# umodular_mega_shield_rev02.net
KiCad netlist of a schematic drawn in EAGLE
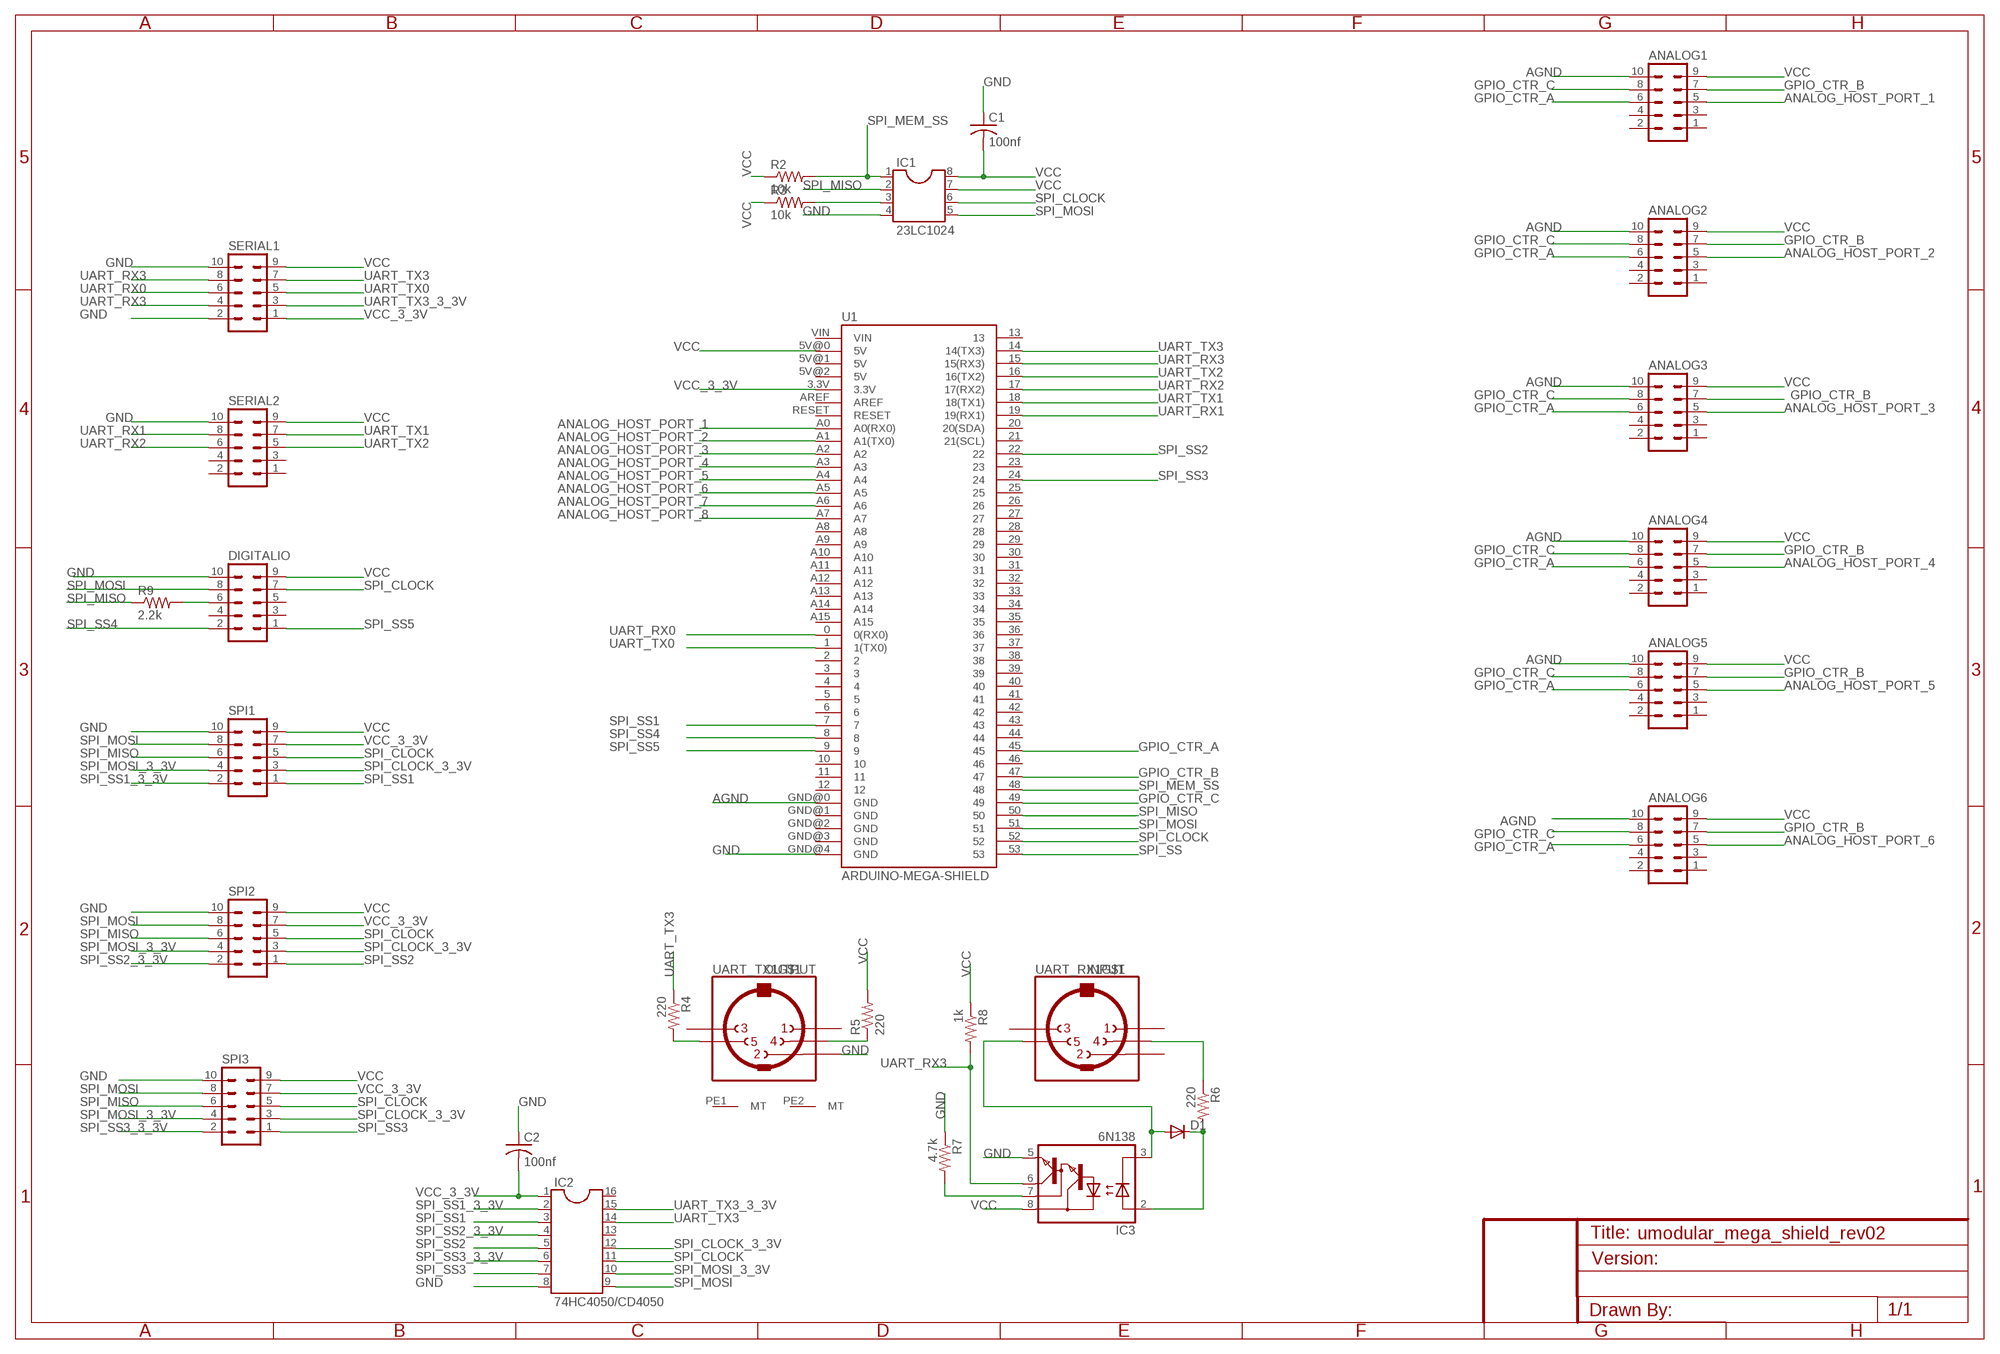
[diagram p0: schematic, sheet 1]

(export (version "E")
  (design (tool "Eeschema 10.0.6"))
  (components
    (comp (ref "ANALOG1")
      (value "MA05-2")
      (footprint "eagle-import:MA05-2")
      (libsource (lib "eagle-import") (part "MA05-2"))
    )
    (comp (ref "ANALOG2")
      (value "MA05-2")
      (footprint "eagle-import:MA05-2")
      (libsource (lib "eagle-import") (part "MA05-2"))
    )
    (comp (ref "ANALOG3")
      (value "MA05-2")
      (footprint "eagle-import:MA05-2")
      (libsource (lib "eagle-import") (part "MA05-2"))
    )
    (comp (ref "ANALOG4")
      (value "MA05-2")
      (footprint "eagle-import:MA05-2")
      (libsource (lib "eagle-import") (part "MA05-2"))
    )
    (comp (ref "ANALOG5")
      (value "MA05-2")
      (footprint "eagle-import:MA05-2")
      (libsource (lib "eagle-import") (part "MA05-2"))
    )
    (comp (ref "ANALOG6")
      (value "MA05-2")
      (footprint "eagle-import:MA05-2")
      (libsource (lib "eagle-import") (part "MA05-2"))
    )
    (comp (ref "C1")
      (value "100nf")
      (footprint "eagle-import:C050-024X044")
      (libsource (lib "eagle-import") (part "C-US050-024X044"))
    )
    (comp (ref "C2")
      (value "100nf")
      (footprint "eagle-import:C050-024X044")
      (libsource (lib "eagle-import") (part "C-US050-024X044"))
    )
    (comp (ref "D1")
      (value "1N4148DO35-7")
      (footprint "eagle-import:DO35-7")
      (libsource (lib "eagle-import") (part "1N4148DO35-7"))
    )
    (comp (ref "DIGITALIO")
      (value "MA05-2")
      (footprint "eagle-import:MA05-2")
      (libsource (lib "eagle-import") (part "MA05-2"))
    )
    (comp (ref "IC1")
      (value "23LC1024")
      (footprint "eagle-import:DIL08")
      (libsource (lib "eagle-import") (part "DIL8"))
    )
    (comp (ref "IC2")
      (value "74HC4050/CD4050")
      (footprint "eagle-import:DIL16")
      (libsource (lib "eagle-import") (part "DIL16"))
    )
    (comp (ref "IC3")
      (value "6N138")
      (footprint "eagle-import:DIL08")
      (fields (field (name "MF") "VISHAY/TELEFUNKEN"))
      (libsource (lib "eagle-import") (part "6N138"))
    )
    (comp (ref "R2")
      (value "10k")
      (footprint "eagle-import:0204_7@1")
      (libsource (lib "eagle-import") (part "R-US_0204/7"))
    )
    (comp (ref "R3")
      (value "10k")
      (footprint "eagle-import:0204_7@1")
      (libsource (lib "eagle-import") (part "R-US_0204/7"))
    )
    (comp (ref "R4")
      (value "220")
      (footprint "eagle-import:0204_7@1")
      (libsource (lib "eagle-import") (part "R-US_0204/7"))
    )
    (comp (ref "R5")
      (value "220")
      (footprint "eagle-import:0204_7@1")
      (libsource (lib "eagle-import") (part "R-US_0204/7"))
    )
    (comp (ref "R6")
      (value "220")
      (footprint "eagle-import:0204_7@1")
      (libsource (lib "eagle-import") (part "R-US_0204/7"))
    )
    (comp (ref "R7")
      (value "4.7k")
      (footprint "eagle-import:0204_7@1")
      (libsource (lib "eagle-import") (part "R-US_0204/7"))
    )
    (comp (ref "R8")
      (value "1k")
      (footprint "eagle-import:0204_7@1")
      (libsource (lib "eagle-import") (part "R-US_0204/7"))
    )
    (comp (ref "R9")
      (value "2.2k")
      (footprint "eagle-import:0204_7@1")
      (libsource (lib "eagle-import") (part "R-US_0204/7"))
    )
    (comp (ref "SERIAL1")
      (value "MA05-2")
      (footprint "eagle-import:MA05-2")
      (libsource (lib "eagle-import") (part "MA05-2"))
    )
    (comp (ref "SERIAL2")
      (value "MA05-2")
      (footprint "eagle-import:MA05-2")
      (libsource (lib "eagle-import") (part "MA05-2"))
    )
    (comp (ref "SPI1")
      (value "MA05-2")
      (footprint "eagle-import:MA05-2")
      (libsource (lib "eagle-import") (part "MA05-2"))
    )
    (comp (ref "SPI2")
      (value "MA05-2")
      (footprint "eagle-import:MA05-2")
      (libsource (lib "eagle-import") (part "MA05-2"))
    )
    (comp (ref "SPI3")
      (value "MA05-2")
      (footprint "eagle-import:MA05-2")
      (libsource (lib "eagle-import") (part "MA05-2"))
    )
    (comp (ref "U1")
      (value "ARDUINO-MEGA-SHIELD")
      (footprint "eagle-import:ARDUINO_MEGA@1")
      (libsource (lib "eagle-import") (part "ARDUINO-MEGAFULL"))
    )
    (comp (ref "UART_RX1")
      (value "INPUT")
      (footprint "eagle-import:CP-2350")
      (libsource (lib "eagle-import") (part "MIDIJACK"))
    )
    (comp (ref "UART_TX1")
      (value "OUTPUT")
      (footprint "eagle-import:CP-2350")
      (libsource (lib "eagle-import") (part "MIDIJACK"))
    )
  )
  (nets
    (net (code "1") (name "/AGND") (class "Default")
      (node (ref "ANALOG1") (pin "10") (pinfunction "10_10") (pintype "passive"))
      (node (ref "ANALOG2") (pin "10") (pinfunction "10_10") (pintype "passive"))
      (node (ref "ANALOG3") (pin "10") (pinfunction "10_10") (pintype "passive"))
      (node (ref "ANALOG4") (pin "10") (pinfunction "10_10") (pintype "passive"))
      (node (ref "ANALOG5") (pin "10") (pinfunction "10_10") (pintype "passive"))
      (node (ref "ANALOG6") (pin "10") (pinfunction "10_10") (pintype "passive"))
      (node (ref "U1") (pin "GND@0") (pinfunction "GND_GND@0") (pintype "bidirectional"))
    )
    (net (code "2") (name "/ANALOG_HOST_PORT_1") (class "Default")
      (node (ref "ANALOG1") (pin "5") (pinfunction "5_5") (pintype "passive"))
      (node (ref "U1") (pin "A0") (pinfunction "A0(RX0)_A0") (pintype "bidirectional"))
    )
    (net (code "3") (name "/ANALOG_HOST_PORT_2") (class "Default")
      (node (ref "ANALOG2") (pin "5") (pinfunction "5_5") (pintype "passive"))
      (node (ref "U1") (pin "A1") (pinfunction "A1(TX0)_A1") (pintype "bidirectional"))
    )
    (net (code "4") (name "/ANALOG_HOST_PORT_3") (class "Default")
      (node (ref "ANALOG3") (pin "5") (pinfunction "5_5") (pintype "passive"))
      (node (ref "U1") (pin "A2") (pinfunction "A2_A2") (pintype "bidirectional"))
    )
    (net (code "5") (name "/ANALOG_HOST_PORT_4") (class "Default")
      (node (ref "ANALOG4") (pin "5") (pinfunction "5_5") (pintype "passive"))
      (node (ref "U1") (pin "A3") (pinfunction "A3_A3") (pintype "bidirectional"))
    )
    (net (code "6") (name "/ANALOG_HOST_PORT_5") (class "Default")
      (node (ref "ANALOG5") (pin "5") (pinfunction "5_5") (pintype "passive"))
      (node (ref "U1") (pin "A4") (pinfunction "A4_A4") (pintype "bidirectional"))
    )
    (net (code "7") (name "/ANALOG_HOST_PORT_6") (class "Default")
      (node (ref "ANALOG6") (pin "5") (pinfunction "5_5") (pintype "passive"))
      (node (ref "U1") (pin "A5") (pinfunction "A5_A5") (pintype "bidirectional"))
    )
    (net (code "8") (name "/ANALOG_HOST_PORT_7") (class "Default")
      (node (ref "U1") (pin "A6") (pinfunction "A6_A6") (pintype "bidirectional"))
    )
    (net (code "9") (name "/ANALOG_HOST_PORT_8") (class "Default")
      (node (ref "U1") (pin "A7") (pinfunction "A7_A7") (pintype "bidirectional"))
    )
    (net (code "10") (name "/GND") (class "Default")
      (node (ref "C1") (pin "1") (pinfunction "1_1") (pintype "passive"))
      (node (ref "C2") (pin "1") (pinfunction "1_1") (pintype "passive"))
      (node (ref "DIGITALIO") (pin "10") (pinfunction "10_10") (pintype "passive"))
      (node (ref "IC1") (pin "4") (pinfunction "4_4") (pintype "passive"))
      (node (ref "IC2") (pin "8") (pinfunction "8_8") (pintype "passive"))
      (node (ref "IC3") (pin "5") (pinfunction "GND_5") (pintype "passive"))
      (node (ref "R7") (pin "1") (pinfunction "1_1") (pintype "passive"))
      (node (ref "SERIAL1") (pin "10") (pinfunction "10_10") (pintype "passive"))
      (node (ref "SERIAL1") (pin "2") (pinfunction "2_2") (pintype "passive"))
      (node (ref "SERIAL2") (pin "10") (pinfunction "10_10") (pintype "passive"))
      (node (ref "SPI1") (pin "10") (pinfunction "10_10") (pintype "passive"))
      (node (ref "SPI2") (pin "10") (pinfunction "10_10") (pintype "passive"))
      (node (ref "SPI3") (pin "10") (pinfunction "10_10") (pintype "passive"))
      (node (ref "U1") (pin "GND@4") (pinfunction "GND_GND@4") (pintype "bidirectional"))
      (node (ref "UART_TX1") (pin "2") (pinfunction "2_2") (pintype "passive"))
    )
    (net (code "11") (name "/GPIO_CTR_A") (class "Default")
      (node (ref "ANALOG1") (pin "6") (pinfunction "6_6") (pintype "passive"))
      (node (ref "ANALOG2") (pin "6") (pinfunction "6_6") (pintype "passive"))
      (node (ref "ANALOG3") (pin "6") (pinfunction "6_6") (pintype "passive"))
      (node (ref "ANALOG4") (pin "6") (pinfunction "6_6") (pintype "passive"))
      (node (ref "ANALOG5") (pin "6") (pinfunction "6_6") (pintype "passive"))
      (node (ref "ANALOG6") (pin "6") (pinfunction "6_6") (pintype "passive"))
      (node (ref "U1") (pin "45") (pinfunction "45_45") (pintype "bidirectional"))
    )
    (net (code "12") (name "/GPIO_CTR_B") (class "Default")
      (node (ref "ANALOG1") (pin "7") (pinfunction "7_7") (pintype "passive"))
      (node (ref "ANALOG2") (pin "7") (pinfunction "7_7") (pintype "passive"))
      (node (ref "ANALOG3") (pin "7") (pinfunction "7_7") (pintype "passive"))
      (node (ref "ANALOG4") (pin "7") (pinfunction "7_7") (pintype "passive"))
      (node (ref "ANALOG5") (pin "7") (pinfunction "7_7") (pintype "passive"))
      (node (ref "ANALOG6") (pin "7") (pinfunction "7_7") (pintype "passive"))
      (node (ref "U1") (pin "47") (pinfunction "47_47") (pintype "bidirectional"))
    )
    (net (code "13") (name "/GPIO_CTR_C") (class "Default")
      (node (ref "ANALOG1") (pin "8") (pinfunction "8_8") (pintype "passive"))
      (node (ref "ANALOG2") (pin "8") (pinfunction "8_8") (pintype "passive"))
      (node (ref "ANALOG3") (pin "8") (pinfunction "8_8") (pintype "passive"))
      (node (ref "ANALOG4") (pin "8") (pinfunction "8_8") (pintype "passive"))
      (node (ref "ANALOG5") (pin "8") (pinfunction "8_8") (pintype "passive"))
      (node (ref "ANALOG6") (pin "8") (pinfunction "8_8") (pintype "passive"))
      (node (ref "U1") (pin "49") (pinfunction "49_49") (pintype "bidirectional"))
    )
    (net (code "14") (name "/SPI_CLOCK") (class "Default")
      (node (ref "DIGITALIO") (pin "7") (pinfunction "7_7") (pintype "passive"))
      (node (ref "IC1") (pin "6") (pinfunction "6_6") (pintype "passive"))
      (node (ref "IC2") (pin "11") (pinfunction "11_11") (pintype "passive"))
      (node (ref "SPI1") (pin "5") (pinfunction "5_5") (pintype "passive"))
      (node (ref "SPI2") (pin "5") (pinfunction "5_5") (pintype "passive"))
      (node (ref "SPI3") (pin "5") (pinfunction "5_5") (pintype "passive"))
      (node (ref "U1") (pin "52") (pinfunction "52_52") (pintype "bidirectional"))
    )
    (net (code "15") (name "/SPI_CLOCK_3_3V") (class "Default")
      (node (ref "IC2") (pin "12") (pinfunction "12_12") (pintype "passive"))
      (node (ref "SPI1") (pin "3") (pinfunction "3_3") (pintype "passive"))
      (node (ref "SPI2") (pin "3") (pinfunction "3_3") (pintype "passive"))
      (node (ref "SPI3") (pin "3") (pinfunction "3_3") (pintype "passive"))
    )
    (net (code "16") (name "/SPI_MEM_SS") (class "Default")
      (node (ref "IC1") (pin "1") (pinfunction "1_1") (pintype "passive"))
      (node (ref "R2") (pin "2") (pinfunction "2_2") (pintype "passive"))
      (node (ref "U1") (pin "48") (pinfunction "48_48") (pintype "bidirectional"))
    )
    (net (code "17") (name "/SPI_MISO") (class "Default")
      (node (ref "IC1") (pin "2") (pinfunction "2_2") (pintype "passive"))
      (node (ref "R9") (pin "1") (pinfunction "1_1") (pintype "passive"))
      (node (ref "SPI1") (pin "6") (pinfunction "6_6") (pintype "passive"))
      (node (ref "SPI2") (pin "6") (pinfunction "6_6") (pintype "passive"))
      (node (ref "SPI3") (pin "6") (pinfunction "6_6") (pintype "passive"))
      (node (ref "U1") (pin "50") (pinfunction "50_50") (pintype "bidirectional"))
    )
    (net (code "18") (name "/SPI_MOSI") (class "Default")
      (node (ref "DIGITALIO") (pin "8") (pinfunction "8_8") (pintype "passive"))
      (node (ref "IC1") (pin "5") (pinfunction "5_5") (pintype "passive"))
      (node (ref "IC2") (pin "9") (pinfunction "9_9") (pintype "passive"))
      (node (ref "SPI1") (pin "8") (pinfunction "8_8") (pintype "passive"))
      (node (ref "SPI2") (pin "8") (pinfunction "8_8") (pintype "passive"))
      (node (ref "SPI3") (pin "8") (pinfunction "8_8") (pintype "passive"))
      (node (ref "U1") (pin "51") (pinfunction "51_51") (pintype "bidirectional"))
    )
    (net (code "19") (name "/SPI_MOSI_3_3V") (class "Default")
      (node (ref "IC2") (pin "10") (pinfunction "10_10") (pintype "passive"))
      (node (ref "SPI1") (pin "4") (pinfunction "4_4") (pintype "passive"))
      (node (ref "SPI2") (pin "4") (pinfunction "4_4") (pintype "passive"))
      (node (ref "SPI3") (pin "4") (pinfunction "4_4") (pintype "passive"))
    )
    (net (code "20") (name "/SPI_SS") (class "Default")
      (node (ref "U1") (pin "53") (pinfunction "53_53") (pintype "bidirectional"))
    )
    (net (code "21") (name "/SPI_SS1") (class "Default")
      (node (ref "IC2") (pin "3") (pinfunction "3_3") (pintype "passive"))
      (node (ref "SPI1") (pin "1") (pinfunction "1_1") (pintype "passive"))
      (node (ref "U1") (pin "7") (pinfunction "7_7") (pintype "bidirectional"))
    )
    (net (code "22") (name "/SPI_SS1_3_3V") (class "Default")
      (node (ref "IC2") (pin "2") (pinfunction "2_2") (pintype "passive"))
      (node (ref "SPI1") (pin "2") (pinfunction "2_2") (pintype "passive"))
    )
    (net (code "23") (name "/SPI_SS2") (class "Default")
      (node (ref "IC2") (pin "5") (pinfunction "5_5") (pintype "passive"))
      (node (ref "SPI2") (pin "1") (pinfunction "1_1") (pintype "passive"))
      (node (ref "U1") (pin "22") (pinfunction "22_22") (pintype "bidirectional"))
    )
    (net (code "24") (name "/SPI_SS2_3_3V") (class "Default")
      (node (ref "IC2") (pin "4") (pinfunction "4_4") (pintype "passive"))
      (node (ref "SPI2") (pin "2") (pinfunction "2_2") (pintype "passive"))
    )
    (net (code "25") (name "/SPI_SS3") (class "Default")
      (node (ref "IC2") (pin "7") (pinfunction "7_7") (pintype "passive"))
      (node (ref "SPI3") (pin "1") (pinfunction "1_1") (pintype "passive"))
      (node (ref "U1") (pin "24") (pinfunction "24_24") (pintype "bidirectional"))
    )
    (net (code "26") (name "/SPI_SS3_3_3V") (class "Default")
      (node (ref "IC2") (pin "6") (pinfunction "6_6") (pintype "passive"))
      (node (ref "SPI3") (pin "2") (pinfunction "2_2") (pintype "passive"))
    )
    (net (code "27") (name "/SPI_SS4") (class "Default")
      (node (ref "DIGITALIO") (pin "2") (pinfunction "2_2") (pintype "passive"))
      (node (ref "U1") (pin "8") (pinfunction "8_8") (pintype "bidirectional"))
    )
    (net (code "28") (name "/SPI_SS5") (class "Default")
      (node (ref "DIGITALIO") (pin "1") (pinfunction "1_1") (pintype "passive"))
      (node (ref "U1") (pin "9") (pinfunction "9_9") (pintype "bidirectional"))
    )
    (net (code "29") (name "/UART_RX0") (class "Default")
      (node (ref "SERIAL1") (pin "6") (pinfunction "6_6") (pintype "passive"))
      (node (ref "U1") (pin "0") (pinfunction "0(RX0)_0") (pintype "bidirectional"))
    )
    (net (code "30") (name "/UART_RX1") (class "Default")
      (node (ref "SERIAL2") (pin "8") (pinfunction "8_8") (pintype "passive"))
      (node (ref "U1") (pin "19") (pinfunction "19(RX1)_19") (pintype "bidirectional"))
    )
    (net (code "31") (name "/UART_RX2") (class "Default")
      (node (ref "SERIAL2") (pin "6") (pinfunction "6_6") (pintype "passive"))
      (node (ref "U1") (pin "17") (pinfunction "17(RX2)_17") (pintype "bidirectional"))
    )
    (net (code "32") (name "/UART_RX3") (class "Default")
      (node (ref "IC3") (pin "6") (pinfunction "VO_6") (pintype "passive"))
      (node (ref "R8") (pin "2") (pinfunction "2_2") (pintype "passive"))
      (node (ref "SERIAL1") (pin "4") (pinfunction "4_4") (pintype "passive"))
      (node (ref "SERIAL1") (pin "8") (pinfunction "8_8") (pintype "passive"))
      (node (ref "U1") (pin "15") (pinfunction "15(RX3)_15") (pintype "bidirectional"))
    )
    (net (code "33") (name "/UART_TX0") (class "Default")
      (node (ref "SERIAL1") (pin "5") (pinfunction "5_5") (pintype "passive"))
      (node (ref "U1") (pin "1") (pinfunction "1(TX0)_1") (pintype "bidirectional"))
    )
    (net (code "34") (name "/UART_TX1") (class "Default")
      (node (ref "SERIAL2") (pin "7") (pinfunction "7_7") (pintype "passive"))
      (node (ref "U1") (pin "18") (pinfunction "18(TX1)_18") (pintype "bidirectional"))
    )
    (net (code "35") (name "/UART_TX2") (class "Default")
      (node (ref "SERIAL2") (pin "5") (pinfunction "5_5") (pintype "passive"))
      (node (ref "U1") (pin "16") (pinfunction "16(TX2)_16") (pintype "bidirectional"))
    )
    (net (code "36") (name "/UART_TX3") (class "Default")
      (node (ref "IC2") (pin "14") (pinfunction "14_14") (pintype "passive"))
      (node (ref "R4") (pin "1") (pinfunction "1_1") (pintype "passive"))
      (node (ref "SERIAL1") (pin "7") (pinfunction "7_7") (pintype "passive"))
      (node (ref "U1") (pin "14") (pinfunction "14(TX3)_14") (pintype "bidirectional"))
    )
    (net (code "37") (name "/UART_TX3_3_3V") (class "Default")
      (node (ref "IC2") (pin "15") (pinfunction "15_15") (pintype "passive"))
      (node (ref "SERIAL1") (pin "3") (pinfunction "3_3") (pintype "passive"))
    )
    (net (code "38") (name "/VCC") (class "Default")
      (node (ref "ANALOG1") (pin "9") (pinfunction "9_9") (pintype "passive"))
      (node (ref "ANALOG2") (pin "9") (pinfunction "9_9") (pintype "passive"))
      (node (ref "ANALOG3") (pin "9") (pinfunction "9_9") (pintype "passive"))
      (node (ref "ANALOG4") (pin "9") (pinfunction "9_9") (pintype "passive"))
      (node (ref "ANALOG5") (pin "9") (pinfunction "9_9") (pintype "passive"))
      (node (ref "ANALOG6") (pin "9") (pinfunction "9_9") (pintype "passive"))
      (node (ref "C1") (pin "2") (pinfunction "2_2") (pintype "passive"))
      (node (ref "DIGITALIO") (pin "9") (pinfunction "9_9") (pintype "passive"))
      (node (ref "IC1") (pin "7") (pinfunction "7_7") (pintype "passive"))
      (node (ref "IC1") (pin "8") (pinfunction "8_8") (pintype "passive"))
      (node (ref "IC3") (pin "8") (pinfunction "VCC_8") (pintype "passive"))
      (node (ref "R2") (pin "1") (pinfunction "1_1") (pintype "passive"))
      (node (ref "R3") (pin "1") (pinfunction "1_1") (pintype "passive"))
      (node (ref "R5") (pin "2") (pinfunction "2_2") (pintype "passive"))
      (node (ref "R8") (pin "1") (pinfunction "1_1") (pintype "passive"))
      (node (ref "SERIAL1") (pin "9") (pinfunction "9_9") (pintype "passive"))
      (node (ref "SERIAL2") (pin "9") (pinfunction "9_9") (pintype "passive"))
      (node (ref "SPI1") (pin "9") (pinfunction "9_9") (pintype "passive"))
      (node (ref "SPI2") (pin "9") (pinfunction "9_9") (pintype "passive"))
      (node (ref "SPI3") (pin "9") (pinfunction "9_9") (pintype "passive"))
      (node (ref "U1") (pin "5V@0") (pinfunction "5V_5V@0") (pintype "bidirectional"))
    )
    (net (code "39") (name "/VCC_3_3V") (class "Default")
      (node (ref "C2") (pin "2") (pinfunction "2_2") (pintype "passive"))
      (node (ref "IC2") (pin "1") (pinfunction "1_1") (pintype "passive"))
      (node (ref "SERIAL1") (pin "1") (pinfunction "1_1") (pintype "passive"))
      (node (ref "SPI1") (pin "7") (pinfunction "7_7") (pintype "passive"))
      (node (ref "SPI2") (pin "7") (pinfunction "7_7") (pintype "passive"))
      (node (ref "SPI3") (pin "7") (pinfunction "7_7") (pintype "passive"))
      (node (ref "U1") (pin "3.3V") (pinfunction "3.3V_3.3V") (pintype "bidirectional"))
    )
    (net (code "40") (name "Net-(DIGITALIO-Pad6)") (class "Default")
      (node (ref "DIGITALIO") (pin "6") (pinfunction "6_6") (pintype "passive"))
      (node (ref "R9") (pin "2") (pinfunction "2_2") (pintype "passive"))
    )
    (net (code "41") (name "Net-(IC1-Pad3)") (class "Default")
      (node (ref "IC1") (pin "3") (pinfunction "3_3") (pintype "passive"))
      (node (ref "R3") (pin "2") (pinfunction "2_2") (pintype "passive"))
    )
    (net (code "42") (name "Net-(IC3-A)") (class "Default")
      (node (ref "D1") (pin "C") (pinfunction "C_C") (pintype "passive"))
      (node (ref "IC3") (pin "2") (pinfunction "A_2") (pintype "passive"))
      (node (ref "R6") (pin "2") (pinfunction "2_2") (pintype "passive"))
    )
    (net (code "43") (name "Net-(IC3-C)") (class "Default")
      (node (ref "D1") (pin "A") (pinfunction "A_A") (pintype "passive"))
      (node (ref "IC3") (pin "3") (pinfunction "C_3") (pintype "passive"))
      (node (ref "UART_RX1") (pin "5") (pinfunction "5_5") (pintype "passive"))
    )
    (net (code "44") (name "Net-(IC3-VB)") (class "Default")
      (node (ref "IC3") (pin "7") (pinfunction "VB_7") (pintype "passive"))
      (node (ref "R7") (pin "2") (pinfunction "2_2") (pintype "passive"))
    )
    (net (code "45") (name "Net-(R4-Pad2)") (class "Default")
      (node (ref "R4") (pin "2") (pinfunction "2_2") (pintype "passive"))
      (node (ref "UART_TX1") (pin "5") (pinfunction "5_5") (pintype "passive"))
    )
    (net (code "46") (name "Net-(R5-Pad1)") (class "Default")
      (node (ref "R5") (pin "1") (pinfunction "1_1") (pintype "passive"))
      (node (ref "UART_TX1") (pin "4") (pinfunction "4_4") (pintype "passive"))
    )
    (net (code "47") (name "Net-(R6-Pad1)") (class "Default")
      (node (ref "R6") (pin "1") (pinfunction "1_1") (pintype "passive"))
      (node (ref "UART_RX1") (pin "4") (pinfunction "4_4") (pintype "passive"))
    )
    (net (code "48") (name "unconnected-(ANALOG1-Pad1)") (class "Default")
      (node (ref "ANALOG1") (pin "1") (pinfunction "1_1") (pintype "passive"))
    )
    (net (code "49") (name "unconnected-(ANALOG1-Pad2)") (class "Default")
      (node (ref "ANALOG1") (pin "2") (pinfunction "2_2") (pintype "passive"))
    )
    (net (code "50") (name "unconnected-(ANALOG1-Pad3)") (class "Default")
      (node (ref "ANALOG1") (pin "3") (pinfunction "3_3") (pintype "passive"))
    )
    (net (code "51") (name "unconnected-(ANALOG1-Pad4)") (class "Default")
      (node (ref "ANALOG1") (pin "4") (pinfunction "4_4") (pintype "passive"))
    )
    (net (code "52") (name "unconnected-(ANALOG2-Pad1)") (class "Default")
      (node (ref "ANALOG2") (pin "1") (pinfunction "1_1") (pintype "passive"))
    )
    (net (code "53") (name "unconnected-(ANALOG2-Pad2)") (class "Default")
      (node (ref "ANALOG2") (pin "2") (pinfunction "2_2") (pintype "passive"))
    )
    (net (code "54") (name "unconnected-(ANALOG2-Pad3)") (class "Default")
      (node (ref "ANALOG2") (pin "3") (pinfunction "3_3") (pintype "passive"))
    )
    (net (code "55") (name "unconnected-(ANALOG2-Pad4)") (class "Default")
      (node (ref "ANALOG2") (pin "4") (pinfunction "4_4") (pintype "passive"))
    )
    (net (code "56") (name "unconnected-(ANALOG3-Pad1)") (class "Default")
      (node (ref "ANALOG3") (pin "1") (pinfunction "1_1") (pintype "passive"))
    )
    (net (code "57") (name "unconnected-(ANALOG3-Pad2)") (class "Default")
      (node (ref "ANALOG3") (pin "2") (pinfunction "2_2") (pintype "passive"))
    )
    (net (code "58") (name "unconnected-(ANALOG3-Pad3)") (class "Default")
      (node (ref "ANALOG3") (pin "3") (pinfunction "3_3") (pintype "passive"))
    )
    (net (code "59") (name "unconnected-(ANALOG3-Pad4)") (class "Default")
      (node (ref "ANALOG3") (pin "4") (pinfunction "4_4") (pintype "passive"))
    )
    (net (code "60") (name "unconnected-(ANALOG4-Pad1)") (class "Default")
      (node (ref "ANALOG4") (pin "1") (pinfunction "1_1") (pintype "passive"))
    )
    (net (code "61") (name "unconnected-(ANALOG4-Pad2)") (class "Default")
      (node (ref "ANALOG4") (pin "2") (pinfunction "2_2") (pintype "passive"))
    )
    (net (code "62") (name "unconnected-(ANALOG4-Pad3)") (class "Default")
      (node (ref "ANALOG4") (pin "3") (pinfunction "3_3") (pintype "passive"))
    )
    (net (code "63") (name "unconnected-(ANALOG4-Pad4)") (class "Default")
      (node (ref "ANALOG4") (pin "4") (pinfunction "4_4") (pintype "passive"))
    )
    (net (code "64") (name "unconnected-(ANALOG5-Pad1)") (class "Default")
      (node (ref "ANALOG5") (pin "1") (pinfunction "1_1") (pintype "passive"))
    )
    (net (code "65") (name "unconnected-(ANALOG5-Pad2)") (class "Default")
      (node (ref "ANALOG5") (pin "2") (pinfunction "2_2") (pintype "passive"))
    )
    (net (code "66") (name "unconnected-(ANALOG5-Pad3)") (class "Default")
      (node (ref "ANALOG5") (pin "3") (pinfunction "3_3") (pintype "passive"))
    )
    (net (code "67") (name "unconnected-(ANALOG5-Pad4)") (class "Default")
      (node (ref "ANALOG5") (pin "4") (pinfunction "4_4") (pintype "passive"))
    )
    (net (code "68") (name "unconnected-(ANALOG6-Pad1)") (class "Default")
      (node (ref "ANALOG6") (pin "1") (pinfunction "1_1") (pintype "passive"))
    )
    (net (code "69") (name "unconnected-(ANALOG6-Pad2)") (class "Default")
      (node (ref "ANALOG6") (pin "2") (pinfunction "2_2") (pintype "passive"))
    )
    (net (code "70") (name "unconnected-(ANALOG6-Pad3)") (class "Default")
      (node (ref "ANALOG6") (pin "3") (pinfunction "3_3") (pintype "passive"))
    )
    (net (code "71") (name "unconnected-(ANALOG6-Pad4)") (class "Default")
      (node (ref "ANALOG6") (pin "4") (pinfunction "4_4") (pintype "passive"))
    )
    (net (code "72") (name "unconnected-(DIGITALIO-Pad3)") (class "Default")
      (node (ref "DIGITALIO") (pin "3") (pinfunction "3_3") (pintype "passive"))
    )
    (net (code "73") (name "unconnected-(DIGITALIO-Pad4)") (class "Default")
      (node (ref "DIGITALIO") (pin "4") (pinfunction "4_4") (pintype "passive"))
    )
    (net (code "74") (name "unconnected-(DIGITALIO-Pad5)") (class "Default")
      (node (ref "DIGITALIO") (pin "5") (pinfunction "5_5") (pintype "passive"))
    )
    (net (code "75") (name "unconnected-(IC2-Pad13)") (class "Default")
      (node (ref "IC2") (pin "13") (pinfunction "13_13") (pintype "passive"))
    )
    (net (code "76") (name "unconnected-(IC2-Pad16)") (class "Default")
      (node (ref "IC2") (pin "16") (pinfunction "16_16") (pintype "passive"))
    )
    (net (code "77") (name "unconnected-(SERIAL2-Pad1)") (class "Default")
      (node (ref "SERIAL2") (pin "1") (pinfunction "1_1") (pintype "passive"))
    )
    (net (code "78") (name "unconnected-(SERIAL2-Pad2)") (class "Default")
      (node (ref "SERIAL2") (pin "2") (pinfunction "2_2") (pintype "passive"))
    )
    (net (code "79") (name "unconnected-(SERIAL2-Pad3)") (class "Default")
      (node (ref "SERIAL2") (pin "3") (pinfunction "3_3") (pintype "passive"))
    )
    (net (code "80") (name "unconnected-(SERIAL2-Pad4)") (class "Default")
      (node (ref "SERIAL2") (pin "4") (pinfunction "4_4") (pintype "passive"))
    )
    (net (code "81") (name "unconnected-(U1-5V-Pad5V@1)") (class "Default")
      (node (ref "U1") (pin "5V@1") (pinfunction "5V_5V@1") (pintype "bidirectional"))
    )
    (net (code "82") (name "unconnected-(U1-5V-Pad5V@2)") (class "Default")
      (node (ref "U1") (pin "5V@2") (pinfunction "5V_5V@2") (pintype "bidirectional"))
    )
    (net (code "83") (name "unconnected-(U1-20(SDA)-Pad20)") (class "Default")
      (node (ref "U1") (pin "20") (pinfunction "20(SDA)_20") (pintype "bidirectional"))
    )
    (net (code "84") (name "unconnected-(U1-21(SCL)-Pad21)") (class "Default")
      (node (ref "U1") (pin "21") (pinfunction "21(SCL)_21") (pintype "bidirectional"))
    )
    (net (code "85") (name "unconnected-(U1-GND-PadGND@1)") (class "Default")
      (node (ref "U1") (pin "GND@1") (pinfunction "GND_GND@1") (pintype "bidirectional"))
    )
    (net (code "86") (name "unconnected-(U1-GND-PadGND@2)") (class "Default")
      (node (ref "U1") (pin "GND@2") (pinfunction "GND_GND@2") (pintype "bidirectional"))
    )
    (net (code "87") (name "unconnected-(U1-GND-PadGND@3)") (class "Default")
      (node (ref "U1") (pin "GND@3") (pinfunction "GND_GND@3") (pintype "bidirectional"))
    )
    (net (code "88") (name "unconnected-(U1-Pad2)") (class "Default")
      (node (ref "U1") (pin "2") (pinfunction "2_2") (pintype "bidirectional"))
    )
    (net (code "89") (name "unconnected-(U1-Pad3)") (class "Default")
      (node (ref "U1") (pin "3") (pinfunction "3_3") (pintype "bidirectional"))
    )
    (net (code "90") (name "unconnected-(U1-Pad4)") (class "Default")
      (node (ref "U1") (pin "4") (pinfunction "4_4") (pintype "bidirectional"))
    )
    (net (code "91") (name "unconnected-(U1-Pad5)") (class "Default")
      (node (ref "U1") (pin "5") (pinfunction "5_5") (pintype "bidirectional"))
    )
    (net (code "92") (name "unconnected-(U1-Pad6)") (class "Default")
      (node (ref "U1") (pin "6") (pinfunction "6_6") (pintype "bidirectional"))
    )
    (net (code "93") (name "unconnected-(U1-Pad10)") (class "Default")
      (node (ref "U1") (pin "10") (pinfunction "10_10") (pintype "bidirectional"))
    )
    (net (code "94") (name "unconnected-(U1-Pad11)") (class "Default")
      (node (ref "U1") (pin "11") (pinfunction "11_11") (pintype "bidirectional"))
    )
    (net (code "95") (name "unconnected-(U1-Pad12)") (class "Default")
      (node (ref "U1") (pin "12") (pinfunction "12_12") (pintype "bidirectional"))
    )
    (net (code "96") (name "unconnected-(U1-Pad13)") (class "Default")
      (node (ref "U1") (pin "13") (pinfunction "13_13") (pintype "bidirectional"))
    )
    (net (code "97") (name "unconnected-(U1-Pad23)") (class "Default")
      (node (ref "U1") (pin "23") (pinfunction "23_23") (pintype "bidirectional"))
    )
    (net (code "98") (name "unconnected-(U1-Pad25)") (class "Default")
      (node (ref "U1") (pin "25") (pinfunction "25_25") (pintype "bidirectional"))
    )
    (net (code "99") (name "unconnected-(U1-Pad26)") (class "Default")
      (node (ref "U1") (pin "26") (pinfunction "26_26") (pintype "bidirectional"))
    )
    (net (code "100") (name "unconnected-(U1-Pad27)") (class "Default")
      (node (ref "U1") (pin "27") (pinfunction "27_27") (pintype "bidirectional"))
    )
    (net (code "101") (name "unconnected-(U1-Pad28)") (class "Default")
      (node (ref "U1") (pin "28") (pinfunction "28_28") (pintype "bidirectional"))
    )
    (net (code "102") (name "unconnected-(U1-Pad29)") (class "Default")
      (node (ref "U1") (pin "29") (pinfunction "29_29") (pintype "bidirectional"))
    )
    (net (code "103") (name "unconnected-(U1-Pad30)") (class "Default")
      (node (ref "U1") (pin "30") (pinfunction "30_30") (pintype "bidirectional"))
    )
    (net (code "104") (name "unconnected-(U1-Pad31)") (class "Default")
      (node (ref "U1") (pin "31") (pinfunction "31_31") (pintype "bidirectional"))
    )
    (net (code "105") (name "unconnected-(U1-Pad32)") (class "Default")
      (node (ref "U1") (pin "32") (pinfunction "32_32") (pintype "bidirectional"))
    )
    (net (code "106") (name "unconnected-(U1-Pad33)") (class "Default")
      (node (ref "U1") (pin "33") (pinfunction "33_33") (pintype "bidirectional"))
    )
    (net (code "107") (name "unconnected-(U1-Pad34)") (class "Default")
      (node (ref "U1") (pin "34") (pinfunction "34_34") (pintype "bidirectional"))
    )
    (net (code "108") (name "unconnected-(U1-Pad35)") (class "Default")
      (node (ref "U1") (pin "35") (pinfunction "35_35") (pintype "bidirectional"))
    )
    (net (code "109") (name "unconnected-(U1-Pad36)") (class "Default")
      (node (ref "U1") (pin "36") (pinfunction "36_36") (pintype "bidirectional"))
    )
    (net (code "110") (name "unconnected-(U1-Pad37)") (class "Default")
      (node (ref "U1") (pin "37") (pinfunction "37_37") (pintype "bidirectional"))
    )
    (net (code "111") (name "unconnected-(U1-Pad38)") (class "Default")
      (node (ref "U1") (pin "38") (pinfunction "38_38") (pintype "bidirectional"))
    )
    (net (code "112") (name "unconnected-(U1-Pad39)") (class "Default")
      (node (ref "U1") (pin "39") (pinfunction "39_39") (pintype "bidirectional"))
    )
    (net (code "113") (name "unconnected-(U1-Pad40)") (class "Default")
      (node (ref "U1") (pin "40") (pinfunction "40_40") (pintype "bidirectional"))
    )
    (net (code "114") (name "unconnected-(U1-Pad41)") (class "Default")
      (node (ref "U1") (pin "41") (pinfunction "41_41") (pintype "bidirectional"))
    )
    (net (code "115") (name "unconnected-(U1-Pad42)") (class "Default")
      (node (ref "U1") (pin "42") (pinfunction "42_42") (pintype "bidirectional"))
    )
    (net (code "116") (name "unconnected-(U1-Pad43)") (class "Default")
      (node (ref "U1") (pin "43") (pinfunction "43_43") (pintype "bidirectional"))
    )
    (net (code "117") (name "unconnected-(U1-Pad44)") (class "Default")
      (node (ref "U1") (pin "44") (pinfunction "44_44") (pintype "bidirectional"))
    )
    (net (code "118") (name "unconnected-(U1-Pad46)") (class "Default")
      (node (ref "U1") (pin "46") (pinfunction "46_46") (pintype "bidirectional"))
    )
    (net (code "119") (name "unconnected-(U1-PadA8)") (class "Default")
      (node (ref "U1") (pin "A8") (pinfunction "A8_A8") (pintype "bidirectional"))
    )
    (net (code "120") (name "unconnected-(U1-PadA9)") (class "Default")
      (node (ref "U1") (pin "A9") (pinfunction "A9_A9") (pintype "bidirectional"))
    )
    (net (code "121") (name "unconnected-(U1-PadA10)") (class "Default")
      (node (ref "U1") (pin "A10") (pinfunction "A10_A10") (pintype "bidirectional"))
    )
    (net (code "122") (name "unconnected-(U1-PadA11)") (class "Default")
      (node (ref "U1") (pin "A11") (pinfunction "A11_A11") (pintype "bidirectional"))
    )
    (net (code "123") (name "unconnected-(U1-PadA12)") (class "Default")
      (node (ref "U1") (pin "A12") (pinfunction "A12_A12") (pintype "bidirectional"))
    )
    (net (code "124") (name "unconnected-(U1-PadA13)") (class "Default")
      (node (ref "U1") (pin "A13") (pinfunction "A13_A13") (pintype "bidirectional"))
    )
    (net (code "125") (name "unconnected-(U1-PadA14)") (class "Default")
      (node (ref "U1") (pin "A14") (pinfunction "A14_A14") (pintype "bidirectional"))
    )
    (net (code "126") (name "unconnected-(U1-PadA15)") (class "Default")
      (node (ref "U1") (pin "A15") (pinfunction "A15_A15") (pintype "bidirectional"))
    )
    (net (code "127") (name "unconnected-(U1-PadAREF)") (class "Default")
      (node (ref "U1") (pin "AREF") (pinfunction "AREF_AREF") (pintype "bidirectional"))
    )
    (net (code "128") (name "unconnected-(U1-PadRESET)") (class "Default")
      (node (ref "U1") (pin "RESET") (pinfunction "RESET_RESET") (pintype "bidirectional"))
    )
    (net (code "129") (name "unconnected-(U1-PadVIN)") (class "Default")
      (node (ref "U1") (pin "VIN") (pinfunction "VIN_VIN") (pintype "bidirectional"))
    )
    (net (code "130") (name "unconnected-(UART_RX1-Pad1)") (class "Default")
      (node (ref "UART_RX1") (pin "1") (pinfunction "1_1") (pintype "passive"))
    )
    (net (code "131") (name "unconnected-(UART_RX1-Pad2)") (class "Default")
      (node (ref "UART_RX1") (pin "2") (pinfunction "2_2") (pintype "passive"))
    )
    (net (code "132") (name "unconnected-(UART_RX1-Pad3)") (class "Default")
      (node (ref "UART_RX1") (pin "3") (pinfunction "3_3") (pintype "passive"))
    )
    (net (code "133") (name "unconnected-(UART_TX1-Pad1)") (class "Default")
      (node (ref "UART_TX1") (pin "1") (pinfunction "1_1") (pintype "passive"))
    )
    (net (code "134") (name "unconnected-(UART_TX1-Pad3)") (class "Default")
      (node (ref "UART_TX1") (pin "3") (pinfunction "3_3") (pintype "passive"))
    )
    (net (code "135") (name "unconnected-(UART_TX1D-MT-PadPE1)") (class "Default")
      (node (ref "UART_TX1") (pin "PE1") (pinfunction "MT_PE1") (pintype "passive"))
    )
    (net (code "136") (name "unconnected-(UART_TX1E-MT-PadPE2)") (class "Default")
      (node (ref "UART_TX1") (pin "PE2") (pinfunction "MT_PE2") (pintype "passive"))
    )
  )
)
